# main_board_v003.net
KiCad netlist of a schematic drawn in EAGLE
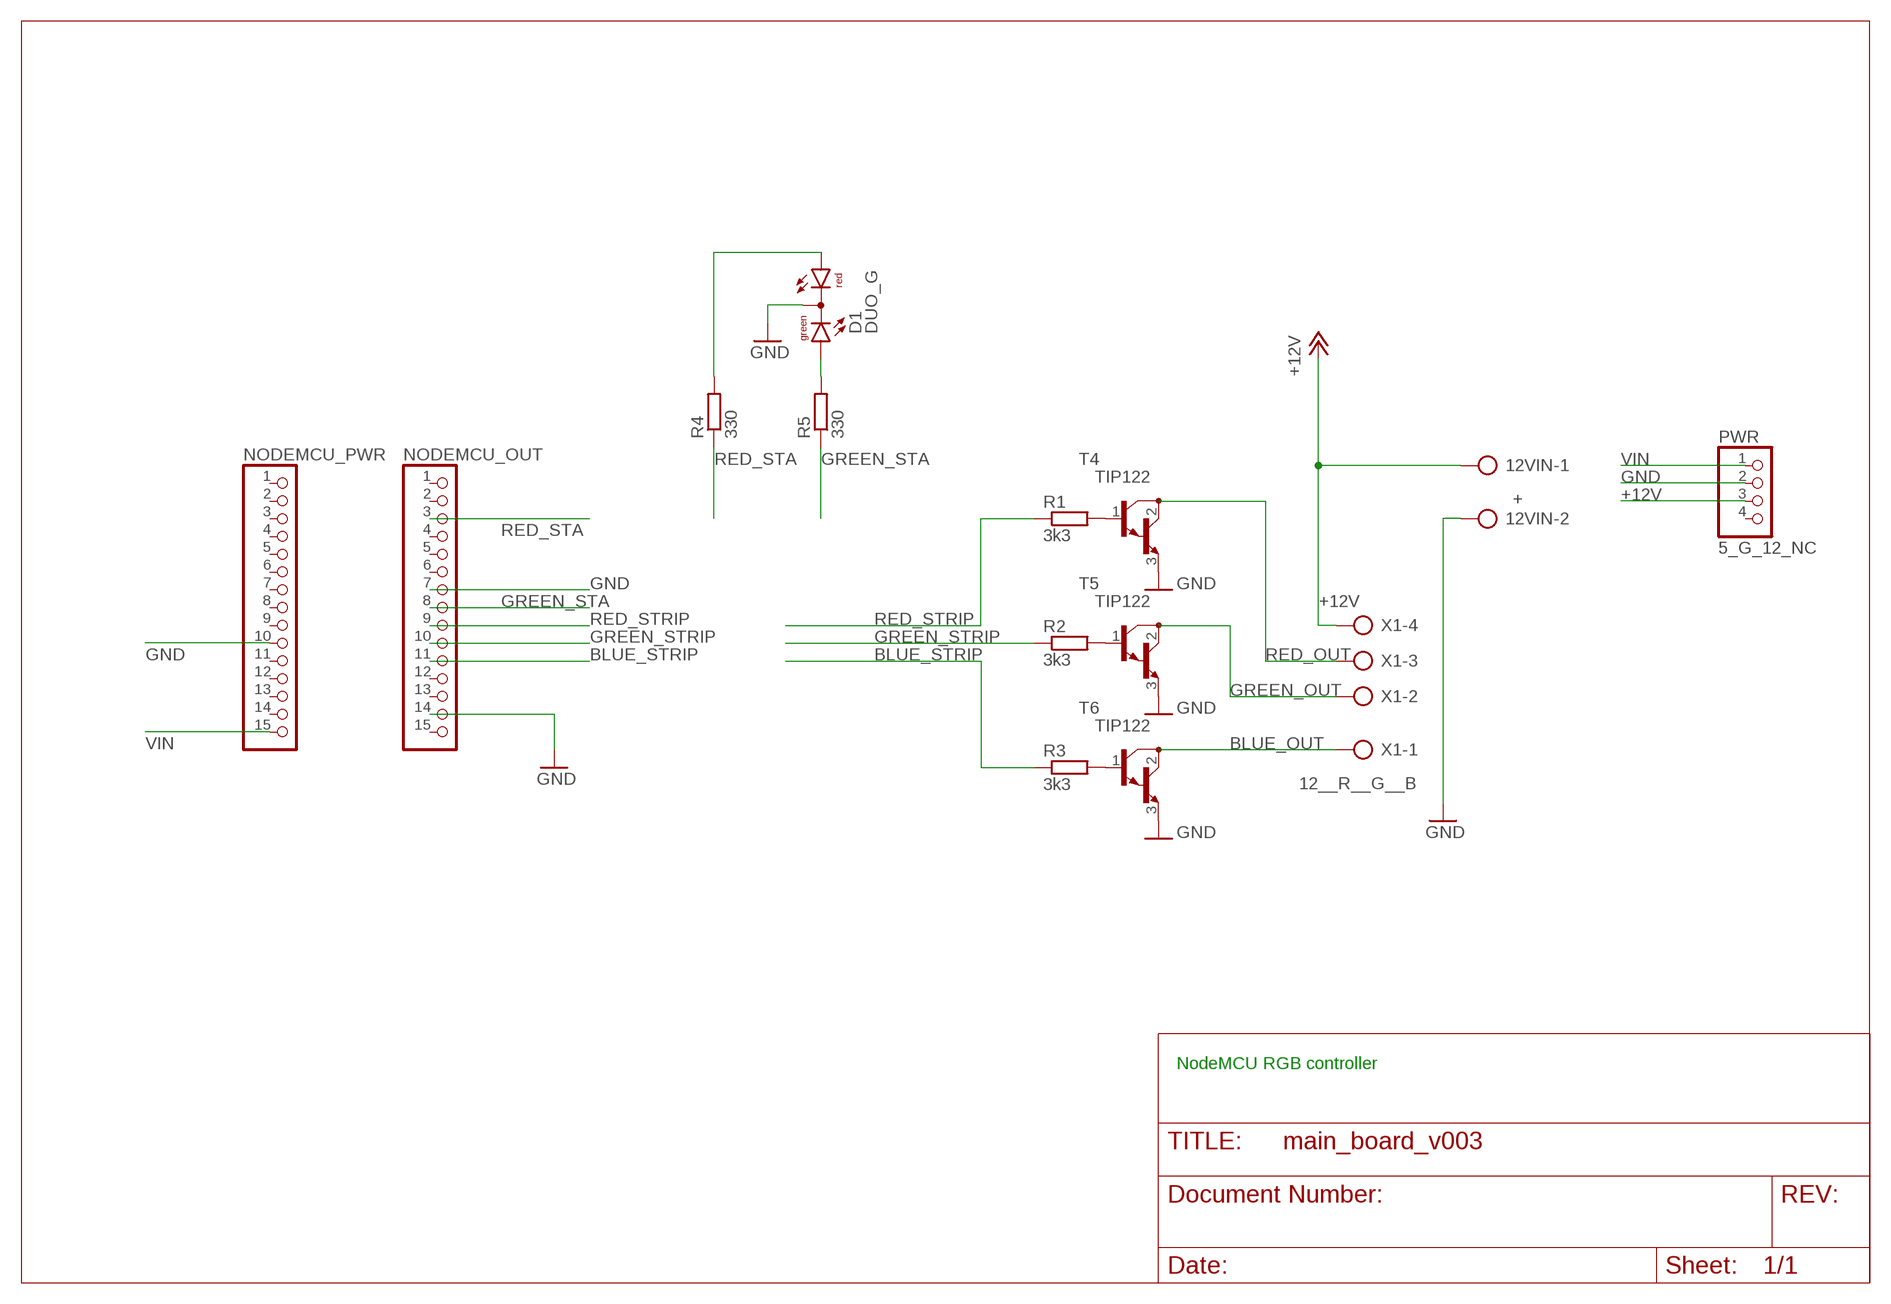
[diagram p0: schematic, sheet 1]

(export (version "E")
  (design (tool "Eeschema 10.0.6"))
  (components
    (comp (ref "12VIN")
      (value "+")
      (footprint "eagle-import:AK500_2-H")
      (libsource (lib "eagle-import") (part "AK500/2-H"))
    )
    (comp (ref "D1")
      (value "DUO_G")
      (footprint "eagle-import:DUOLED2X5")
      (libsource (lib "eagle-import") (part "DUOLED2X5"))
    )
    (comp (ref "NODEMCU_OUT")
      (value "PINHD-1X15")
      (footprint "eagle-import:1X15")
      (libsource (lib "eagle-import") (part "PINHD-1X15"))
    )
    (comp (ref "NODEMCU_PWR")
      (value "PINHD-1X15")
      (footprint "eagle-import:1X15")
      (libsource (lib "eagle-import") (part "PINHD-1X15"))
    )
    (comp (ref "PWR")
      (value "5_G_12_NC")
      (footprint "eagle-import:1X04")
      (libsource (lib "eagle-import") (part "PINHD-1X4"))
    )
    (comp (ref "R1")
      (value "3k3")
      (footprint "eagle-import:0207_10")
      (libsource (lib "eagle-import") (part "R-EU_0207/10"))
    )
    (comp (ref "R2")
      (value "3k3")
      (footprint "eagle-import:0207_10")
      (libsource (lib "eagle-import") (part "R-EU_0207/10"))
    )
    (comp (ref "R3")
      (value "3k3")
      (footprint "eagle-import:0207_10")
      (libsource (lib "eagle-import") (part "R-EU_0207/10"))
    )
    (comp (ref "R4")
      (value "330")
      (footprint "eagle-import:0207_10")
      (libsource (lib "eagle-import") (part "R-EU_0207/10"))
    )
    (comp (ref "R5")
      (value "330")
      (footprint "eagle-import:0207_10")
      (libsource (lib "eagle-import") (part "R-EU_0207/10"))
    )
    (comp (ref "T4")
      (value "TIP122")
      (footprint "eagle-import:TO220")
      (libsource (lib "eagle-import") (part "TIP122"))
    )
    (comp (ref "T5")
      (value "TIP122")
      (footprint "eagle-import:TO220")
      (libsource (lib "eagle-import") (part "TIP122"))
    )
    (comp (ref "T6")
      (value "TIP122")
      (footprint "eagle-import:TO220")
      (libsource (lib "eagle-import") (part "TIP122"))
    )
    (comp (ref "X1")
      (value "12__R__G__B")
      (footprint "eagle-import:AK500_4-H")
      (libsource (lib "eagle-import") (part "AK500/4-H"))
    )
  )
  (nets
    (net (code "1") (name "+12V") (class "Default")
      (node (ref "12VIN") (pin "1") (pinfunction "KL_1") (pintype "passive"))
      (node (ref "PWR") (pin "3") (pinfunction "3_3") (pintype "passive"))
      (node (ref "X1") (pin "4") (pinfunction "KL_4") (pintype "passive"))
    )
    (net (code "2") (name "/BLUE_OUT") (class "Default")
      (node (ref "T6") (pin "2") (pinfunction "C_2") (pintype "passive"))
      (node (ref "X1") (pin "1") (pinfunction "KL_1") (pintype "passive"))
    )
    (net (code "3") (name "/BLUE_STRIP") (class "Default")
      (node (ref "NODEMCU_OUT") (pin "11") (pinfunction "11_11") (pintype "passive"))
      (node (ref "R3") (pin "1") (pinfunction "1_1") (pintype "passive"))
    )
    (net (code "4") (name "/GREEN_OUT") (class "Default")
      (node (ref "T5") (pin "2") (pinfunction "C_2") (pintype "passive"))
      (node (ref "X1") (pin "2") (pinfunction "KL_2") (pintype "passive"))
    )
    (net (code "5") (name "/GREEN_STA") (class "Default")
      (node (ref "NODEMCU_OUT") (pin "8") (pinfunction "8_8") (pintype "passive"))
      (node (ref "R5") (pin "1") (pinfunction "1_1") (pintype "passive"))
    )
    (net (code "6") (name "/GREEN_STRIP") (class "Default")
      (node (ref "NODEMCU_OUT") (pin "10") (pinfunction "10_10") (pintype "passive"))
      (node (ref "R2") (pin "1") (pinfunction "1_1") (pintype "passive"))
    )
    (net (code "7") (name "/RED_OUT") (class "Default")
      (node (ref "T4") (pin "2") (pinfunction "C_2") (pintype "passive"))
      (node (ref "X1") (pin "3") (pinfunction "KL_3") (pintype "passive"))
    )
    (net (code "8") (name "/RED_STA") (class "Default")
      (node (ref "NODEMCU_OUT") (pin "3") (pinfunction "3_3") (pintype "passive"))
      (node (ref "R4") (pin "1") (pinfunction "1_1") (pintype "passive"))
    )
    (net (code "9") (name "/RED_STRIP") (class "Default")
      (node (ref "NODEMCU_OUT") (pin "9") (pinfunction "9_9") (pintype "passive"))
      (node (ref "R1") (pin "1") (pinfunction "1_1") (pintype "passive"))
    )
    (net (code "10") (name "/VIN") (class "Default")
      (node (ref "NODEMCU_PWR") (pin "15") (pinfunction "15_15") (pintype "passive"))
      (node (ref "PWR") (pin "1") (pinfunction "1_1") (pintype "passive"))
    )
    (net (code "11") (name "GND") (class "Default")
      (node (ref "12VIN") (pin "2") (pinfunction "KL_2") (pintype "passive"))
      (node (ref "D1") (pin "K") (pinfunction "C_K") (pintype "passive"))
      (node (ref "NODEMCU_OUT") (pin "14") (pinfunction "14_14") (pintype "passive"))
      (node (ref "NODEMCU_OUT") (pin "7") (pinfunction "7_7") (pintype "passive"))
      (node (ref "NODEMCU_PWR") (pin "10") (pinfunction "10_10") (pintype "passive"))
      (node (ref "PWR") (pin "2") (pinfunction "2_2") (pintype "passive"))
      (node (ref "T4") (pin "3") (pinfunction "E_3") (pintype "passive"))
      (node (ref "T5") (pin "3") (pinfunction "E_3") (pintype "passive"))
      (node (ref "T6") (pin "3") (pinfunction "E_3") (pintype "passive"))
    )
    (net (code "12") (name "Net-(D1-PadAG)") (class "Default")
      (node (ref "D1") (pin "AG") (pinfunction "AG_AG") (pintype "passive"))
      (node (ref "R5") (pin "2") (pinfunction "2_2") (pintype "passive"))
    )
    (net (code "13") (name "Net-(D1-PadAR)") (class "Default")
      (node (ref "D1") (pin "AR") (pinfunction "AR_AR") (pintype "passive"))
      (node (ref "R4") (pin "2") (pinfunction "2_2") (pintype "passive"))
    )
    (net (code "14") (name "Net-(T4-B)") (class "Default")
      (node (ref "R1") (pin "2") (pinfunction "2_2") (pintype "passive"))
      (node (ref "T4") (pin "1") (pinfunction "B_1") (pintype "passive"))
    )
    (net (code "15") (name "Net-(T5-B)") (class "Default")
      (node (ref "R2") (pin "2") (pinfunction "2_2") (pintype "passive"))
      (node (ref "T5") (pin "1") (pinfunction "B_1") (pintype "passive"))
    )
    (net (code "16") (name "Net-(T6-B)") (class "Default")
      (node (ref "R3") (pin "2") (pinfunction "2_2") (pintype "passive"))
      (node (ref "T6") (pin "1") (pinfunction "B_1") (pintype "passive"))
    )
    (net (code "17") (name "unconnected-(NODEMCU_OUT-Pad1)") (class "Default")
      (node (ref "NODEMCU_OUT") (pin "1") (pinfunction "1_1") (pintype "passive"))
    )
    (net (code "18") (name "unconnected-(NODEMCU_OUT-Pad2)") (class "Default")
      (node (ref "NODEMCU_OUT") (pin "2") (pinfunction "2_2") (pintype "passive"))
    )
    (net (code "19") (name "unconnected-(NODEMCU_OUT-Pad4)") (class "Default")
      (node (ref "NODEMCU_OUT") (pin "4") (pinfunction "4_4") (pintype "passive"))
    )
    (net (code "20") (name "unconnected-(NODEMCU_OUT-Pad5)") (class "Default")
      (node (ref "NODEMCU_OUT") (pin "5") (pinfunction "5_5") (pintype "passive"))
    )
    (net (code "21") (name "unconnected-(NODEMCU_OUT-Pad6)") (class "Default")
      (node (ref "NODEMCU_OUT") (pin "6") (pinfunction "6_6") (pintype "passive"))
    )
    (net (code "22") (name "unconnected-(NODEMCU_OUT-Pad12)") (class "Default")
      (node (ref "NODEMCU_OUT") (pin "12") (pinfunction "12_12") (pintype "passive"))
    )
    (net (code "23") (name "unconnected-(NODEMCU_OUT-Pad13)") (class "Default")
      (node (ref "NODEMCU_OUT") (pin "13") (pinfunction "13_13") (pintype "passive"))
    )
    (net (code "24") (name "unconnected-(NODEMCU_OUT-Pad15)") (class "Default")
      (node (ref "NODEMCU_OUT") (pin "15") (pinfunction "15_15") (pintype "passive"))
    )
    (net (code "25") (name "unconnected-(NODEMCU_PWR-Pad1)") (class "Default")
      (node (ref "NODEMCU_PWR") (pin "1") (pinfunction "1_1") (pintype "passive"))
    )
    (net (code "26") (name "unconnected-(NODEMCU_PWR-Pad2)") (class "Default")
      (node (ref "NODEMCU_PWR") (pin "2") (pinfunction "2_2") (pintype "passive"))
    )
    (net (code "27") (name "unconnected-(NODEMCU_PWR-Pad3)") (class "Default")
      (node (ref "NODEMCU_PWR") (pin "3") (pinfunction "3_3") (pintype "passive"))
    )
    (net (code "28") (name "unconnected-(NODEMCU_PWR-Pad4)") (class "Default")
      (node (ref "NODEMCU_PWR") (pin "4") (pinfunction "4_4") (pintype "passive"))
    )
    (net (code "29") (name "unconnected-(NODEMCU_PWR-Pad5)") (class "Default")
      (node (ref "NODEMCU_PWR") (pin "5") (pinfunction "5_5") (pintype "passive"))
    )
    (net (code "30") (name "unconnected-(NODEMCU_PWR-Pad6)") (class "Default")
      (node (ref "NODEMCU_PWR") (pin "6") (pinfunction "6_6") (pintype "passive"))
    )
    (net (code "31") (name "unconnected-(NODEMCU_PWR-Pad7)") (class "Default")
      (node (ref "NODEMCU_PWR") (pin "7") (pinfunction "7_7") (pintype "passive"))
    )
    (net (code "32") (name "unconnected-(NODEMCU_PWR-Pad8)") (class "Default")
      (node (ref "NODEMCU_PWR") (pin "8") (pinfunction "8_8") (pintype "passive"))
    )
    (net (code "33") (name "unconnected-(NODEMCU_PWR-Pad9)") (class "Default")
      (node (ref "NODEMCU_PWR") (pin "9") (pinfunction "9_9") (pintype "passive"))
    )
    (net (code "34") (name "unconnected-(NODEMCU_PWR-Pad11)") (class "Default")
      (node (ref "NODEMCU_PWR") (pin "11") (pinfunction "11_11") (pintype "passive"))
    )
    (net (code "35") (name "unconnected-(NODEMCU_PWR-Pad12)") (class "Default")
      (node (ref "NODEMCU_PWR") (pin "12") (pinfunction "12_12") (pintype "passive"))
    )
    (net (code "36") (name "unconnected-(NODEMCU_PWR-Pad13)") (class "Default")
      (node (ref "NODEMCU_PWR") (pin "13") (pinfunction "13_13") (pintype "passive"))
    )
    (net (code "37") (name "unconnected-(NODEMCU_PWR-Pad14)") (class "Default")
      (node (ref "NODEMCU_PWR") (pin "14") (pinfunction "14_14") (pintype "passive"))
    )
    (net (code "38") (name "unconnected-(PWR-Pad4)") (class "Default")
      (node (ref "PWR") (pin "4") (pinfunction "4_4") (pintype "passive"))
    )
  )
)
